# Sheet1.net
KiCad netlist of a schematic drawn in Altium Designer
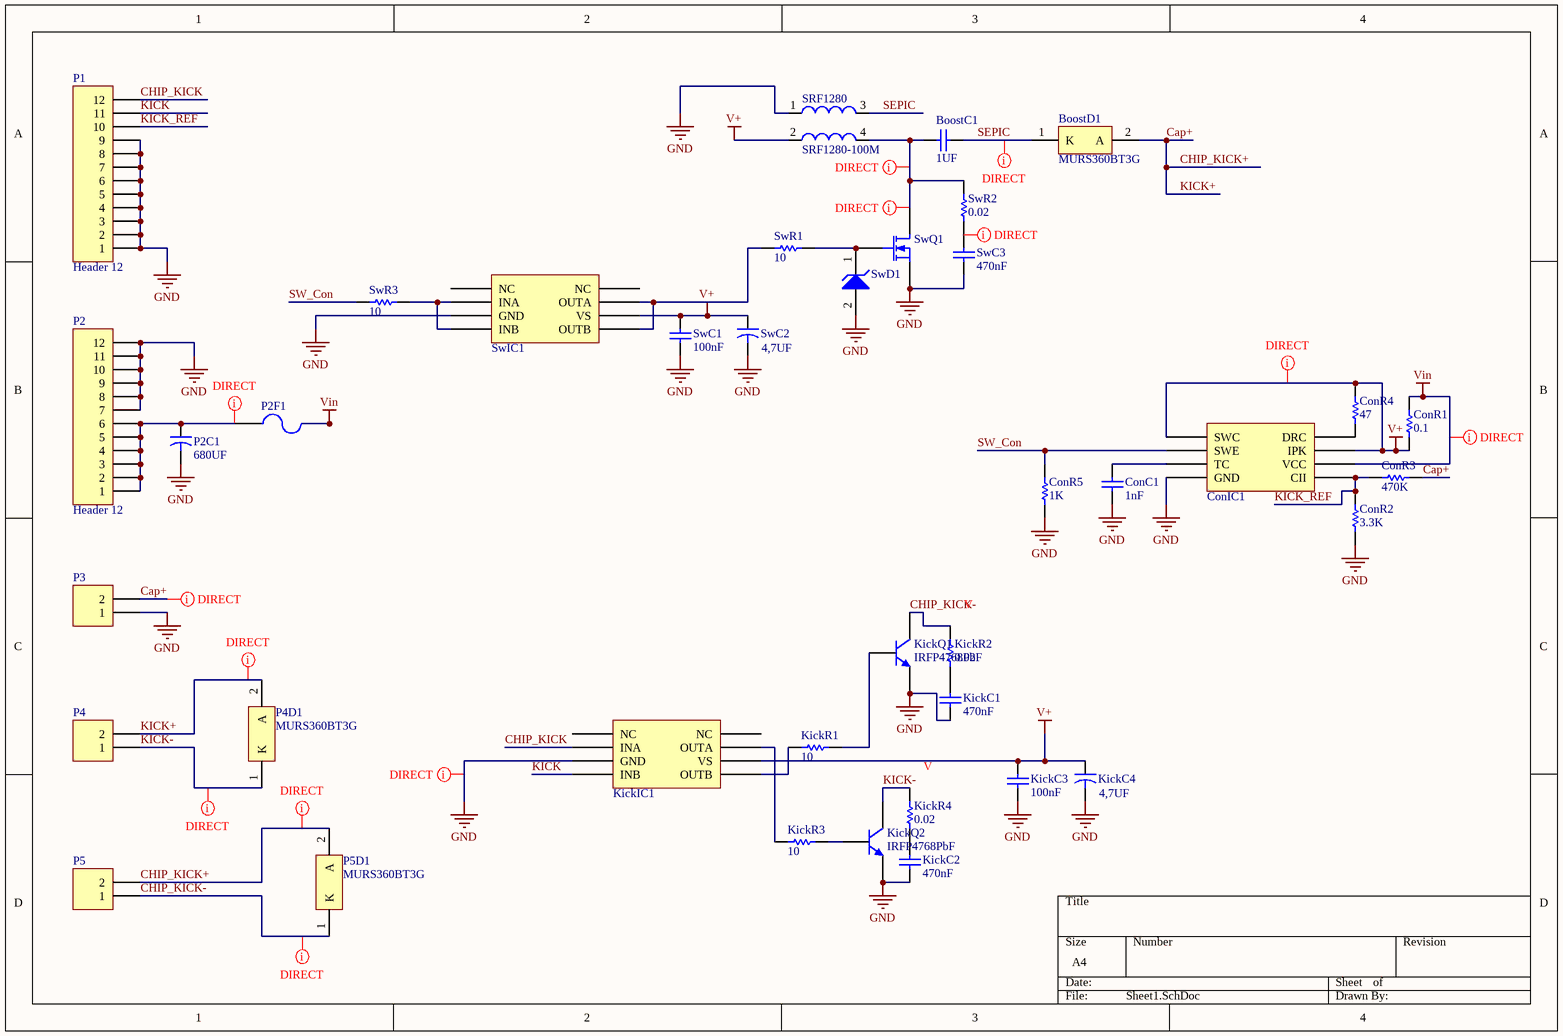
[diagram p0: Sheet1.SchDoc]

(export (version "E")
  (design (tool "Eeschema 10.0.6"))
  (components
    (comp (ref "BoostC1")
      (value "1UF")
      (footprint "CAP-2220")
      (description "1µF 450V Ceramic Capacitor X7T 2220 (5750 Metric) 0.224\" L x 0.197\" W (5.70mm x 5.00mm)")
      (fields (field (name "Comment") "CGA9P4X7T2W105M250KE"))
      (libsource (lib "Schlib1") (part "Cap 1UF 2220 450V"))
    )
    (comp (ref "BoostD1")
      (value "MURS360BT3G")
      (footprint "ONSC-SMB-2-403A-03_V")
      (description "Surface Mount Ultrafast Power Rectifier, 2-Pin SMB, Pb-Free, Tape and Reel")
      (fields (field (name "MANUFACTURER") "On Semiconductor"))
      (libsource (lib "") (part "CMP-0902-00327-1_1"))
    )
    (comp (ref "ConC1")
      (value "1nF")
      (footprint "CAP-0402")
      (description "1000pF 50V Ceramic Capacitor X7R 0402 (1005 Metric) 0.039\" L x 0.020\" W (1.00mm x 0.50mm)")
      (fields (field (name "Comment") "GRM155R71H102KA01D"))
      (libsource (lib "Schlib1") (part "Cap 1nF 0402"))
    )
    (comp (ref "ConIC1")
      (value "MC34063ACD")
      (footprint "SOIC8-STM")
      (libsource (lib "Schlib1") (part "MC34063ACD"))
    )
    (comp (ref "ConR1")
      (value "0.1")
      (footprint "RES-2512 BOURNS CRA")
      (description "RES SMD 0.1 OHM 1% 3W 2512")
      (fields (field (name "Comment") "CRA2512-FZ-R100ELF"))
      (libsource (lib "Schlib1") (part "RES 0R1 2512"))
    )
    (comp (ref "ConR2")
      (value "3.3K")
      (footprint "RES-1206")
      (description "RES SMD 3.3K OHM 5% 1/4W 1206")
      (fields (field (name "Comment") "RC1206JR-073K3L"))
      (libsource (lib "Schlib1") (part "RES 3.3K 1206"))
    )
    (comp (ref "ConR3")
      (value "470K")
      (footprint "RES-1206")
      (description "RES SMD 470K OHM 1% 1/4W 1206")
      (fields (field (name "Comment") "RC1206FR-07470KL"))
      (libsource (lib "Schlib1") (part "RES 470K 1206"))
    )
    (comp (ref "ConR4")
      (value "47")
      (footprint "RES-0402")
      (description "RES SMD 47 OHM 5% 1/16W 0402")
      (fields (field (name "Comment") "RC0402JR-0747RL"))
      (libsource (lib "Schlib1") (part "RES 47 0402"))
    )
    (comp (ref "ConR5")
      (value "1K")
      (footprint "RES-0402")
      (description "RES SMD 1K OHM 5% 1/16W 0402")
      (fields (field (name "Comment") "RC0402JR-071KL"))
      (libsource (lib "Schlib1") (part "RES 1K 0402"))
    )
    (comp (ref "KickC1")
      (value "470nF")
      (footprint "CAP-1812 TDK")
      (description "0.47µF 250V Ceramic Capacitor X7R 1812 (4532 Metric) 0.177\" L x 0.126\" W (4.50mm x 3.20mm)")
      (fields (field (name "Comment") "C4532X7R2E474K230KA"))
      (libsource (lib "Schlib1") (part "Cap 470nF 250V 1812"))
    )
    (comp (ref "KickC2")
      (value "470nF")
      (footprint "CAP-1812 TDK")
      (description "0.47µF 250V Ceramic Capacitor X7R 1812 (4532 Metric) 0.177\" L x 0.126\" W (4.50mm x 3.20mm)")
      (fields (field (name "Comment") "C4532X7R2E474K230KA"))
      (libsource (lib "Schlib1") (part "Cap 470nF 250V 1812"))
    )
    (comp (ref "KickC3")
      (value "100nF")
      (footprint "CAP-0402")
      (description "0.10µF 16V Ceramic Capacitor X7R 0402 (1005 Metric) 0.039\" L x 0.020\" W (1.00mm x 0.50mm)")
      (fields (field (name "Comment") "GRM155R71C104KA88D"))
      (libsource (lib "Schlib1") (part "Cap 100nF 0402"))
    )
    (comp (ref "KickC4")
      (value "4,7UF")
      (footprint "CAP Tant 1206 Kemet")
      (fields (field (name "Comment") "T491A475M025AT"))
      (libsource (lib "Schlib1") (part "Cap Tant 4,7UF 1206"))
    )
    (comp (ref "KickIC1")
      (value "IR4427STRPBF")
      (footprint "SOIC8-INFINEON")
      (description "IC DRIVER DUAL LOW SIDE 8SOIC")
      (libsource (lib "Schlib1") (part "IR4427"))
    )
    (comp (ref "KickQ1")
      (value "IRFP4768PbF")
      (footprint "TO-247AC")
      (description "MOSFET N-CH 250V 93A TO-247AC")
      (libsource (lib "Schlib1") (part "IRG4PC50FD"))
    )
    (comp (ref "KickQ2")
      (value "IRFP4768PbF")
      (footprint "TO-247AC")
      (description "MOSFET N-CH 250V 93A TO-247AC")
      (libsource (lib "Schlib1") (part "IRG4PC50FD"))
    )
    (comp (ref "KickR1")
      (value "10")
      (footprint "RES-0402")
      (description "RES SMD 10 OHM 5% 1/16W 0402")
      (fields (field (name "Comment") "RC0402JR-0710RL"))
      (libsource (lib "Schlib1") (part "RES 10 0402"))
    )
    (comp (ref "KickR2")
      (value "0.02")
      (footprint "RES-1206")
      (description "RES SMD 0.02 OHM 1% 1/4W 1206")
      (fields (field (name "Comment") "PF1206FRF070R02L"))
      (libsource (lib "Schlib1") (part "RES 0R02 1206"))
    )
    (comp (ref "KickR3")
      (value "10")
      (footprint "RES-0402")
      (description "RES SMD 10 OHM 5% 1/16W 0402")
      (fields (field (name "Comment") "RC0402JR-0710RL"))
      (libsource (lib "Schlib1") (part "RES 10 0402"))
    )
    (comp (ref "KickR4")
      (value "0.02")
      (footprint "RES-1206")
      (description "RES SMD 0.02 OHM 1% 1/4W 1206")
      (fields (field (name "Comment") "PF1206FRF070R02L"))
      (libsource (lib "Schlib1") (part "RES 0R02 1206"))
    )
    (comp (ref "P1")
      (value "Header 12")
      (footprint "HDR1X12")
      (description "Header, 12-Pin")
      (fields (field (name "PUBLISHER") "Altium Limited"))
      (libsource (lib "Miscellaneous Connectors") (part "Header 12"))
    )
    (comp (ref "P2")
      (value "Header 12")
      (footprint "HDR1X12")
      (description "Header, 12-Pin")
      (fields (field (name "PUBLISHER") "Altium Limited"))
      (libsource (lib "Miscellaneous Connectors") (part "Header 12"))
    )
    (comp (ref "P2C1")
      (value "680UF")
      (footprint "Cap Al Size G - Panasonic")
      (description "Aluminum Electrolytic Capacitors - SMD Al Lytic Cap SMT FK Series 105C")
      (fields (field (name "Comment") "EEE-FK1C681GP"))
      (libsource (lib "Schlib1") (part "CAP AL 680UF/16V"))
    )
    (comp (ref "P2F1")
      (value "MF-MSMF250/16X-2")
      (footprint "1812-MSMF Bourns2")
      (description "PTC RESETTABLE")
      (libsource (lib "Schlib1") (part "MF-MSMF250/16X"))
    )
    (comp (ref "P3")
      (value "OSTTA024163")
      (footprint "Term Block 2P")
      (description "2 Position Wire to Board Terminal Block Horizontal with Board 0.200\" (5.08mm) Through Hole")
      (libsource (lib "Schlib1") (part "Term Block 2P"))
    )
    (comp (ref "P4")
      (value "OSTTA024163")
      (footprint "Term Block 2P")
      (description "2 Position Wire to Board Terminal Block Horizontal with Board 0.200\" (5.08mm) Through Hole")
      (libsource (lib "Schlib1") (part "Term Block 2P"))
    )
    (comp (ref "P4D1")
      (value "MURS360BT3G")
      (footprint "ONSC-SMB-2-403A-03_V")
      (description "Surface Mount Ultrafast Power Rectifier, 2-Pin SMB, Pb-Free, Tape and Reel")
      (fields (field (name "MANUFACTURER") "On Semiconductor"))
      (libsource (lib "Altium Content Vault") (part "CMP-0902-00327-1"))
    )
    (comp (ref "P5")
      (value "OSTTA024163")
      (footprint "Term Block 2P")
      (description "2 Position Wire to Board Terminal Block Horizontal with Board 0.200\" (5.08mm) Through Hole")
      (libsource (lib "Schlib1") (part "Term Block 2P"))
    )
    (comp (ref "P5D1")
      (value "MURS360BT3G")
      (footprint "ONSC-SMB-2-403A-03_V")
      (description "Surface Mount Ultrafast Power Rectifier, 2-Pin SMB, Pb-Free, Tape and Reel")
      (fields (field (name "MANUFACTURER") "On Semiconductor"))
      (libsource (lib "Altium Content Vault") (part "CMP-0902-00327-1"))
    )
    (comp (ref "SRF1280")
      (value "SRF1280-100M")
      (footprint "SRF1280-100M-PCB")
      (libsource (lib "Schlib1") (part "SRF1280-100M"))
    )
    (comp (ref "SwC1")
      (value "100nF")
      (footprint "CAP-0402")
      (description "0.10µF 16V Ceramic Capacitor X7R 0402 (1005 Metric) 0.039\" L x 0.020\" W (1.00mm x 0.50mm)")
      (fields (field (name "Comment") "GRM155R71C104KA88D"))
      (libsource (lib "Schlib1") (part "Cap 100nF 0402"))
    )
    (comp (ref "SwC2")
      (value "4,7UF")
      (footprint "CAP Tant 1206 Kemet")
      (fields (field (name "Comment") "T491A475M025AT"))
      (libsource (lib "Schlib1") (part "Cap Tant 4,7UF 1206"))
    )
    (comp (ref "SwC3")
      (value "470nF")
      (footprint "CAP-1206 KEMET")
      (description "0.47µF 50V Ceramic Capacitor X8L 1206 (3216 Metric) 0.126\" L x 0.063\" W (3.20mm x 1.60mm)")
      (fields (field (name "Comment") "C1206C474K5NACTU"))
      (libsource (lib "Schlib1") (part "Cap 470nF 50V 1206"))
    )
    (comp (ref "SwD1")
      (value "MMSZ18T1G")
      (footprint "ONSC-SOD-123-2-425-04_V")
      (description "Zener Voltage Regulator, 500 mW, 2-Pin SOD-123, Pb-Free, Tape and Reel")
      (fields (field (name "MANUFACTURER") "On Semiconductor"))
      (libsource (lib "Altium Content Vault") (part "CMP-1060-00279-1"))
    )
    (comp (ref "SwIC1")
      (value "IR4427STRPBF")
      (footprint "SOIC8-INFINEON")
      (description "IC DRIVER DUAL LOW SIDE 8SOIC")
      (libsource (lib "Schlib1") (part "IR4427"))
    )
    (comp (ref "SwQ1")
      (value "SUM45N25-58-E3")
      (footprint "TO-263 Vishay")
      (description "MOSFET N-CH 250V 45A D2PAK")
      (libsource (lib "Schlib1") (part "SUM45N25"))
    )
    (comp (ref "SwR1")
      (value "10")
      (footprint "RES-0402")
      (description "RES SMD 10 OHM 5% 1/16W 0402")
      (fields (field (name "Comment") "RC0402JR-0710RL"))
      (libsource (lib "Schlib1") (part "RES 10 0402"))
    )
    (comp (ref "SwR2")
      (value "0.02")
      (footprint "RES-1206")
      (description "RES SMD 0.02 OHM 1% 1/4W 1206")
      (fields (field (name "Comment") "PF1206FRF070R02L"))
      (libsource (lib "Schlib1") (part "RES 0R02 1206"))
    )
    (comp (ref "SwR3")
      (value "10")
      (footprint "RES-0402")
      (description "RES SMD 10 OHM 5% 1/16W 0402")
      (fields (field (name "Comment") "RC0402JR-0710RL"))
      (libsource (lib "Schlib1") (part "RES 10 0402"))
    )
  )
  (nets
    (net (code "1") (name "/CHIP_KICK") (class "Default")
      (node (ref "KickIC1") (pin "2") (pinfunction "INA_2") (pintype "passive"))
      (node (ref "P1") (pin "12") (pinfunction "12_12") (pintype "passive"))
    )
    (net (code "2") (name "/CHIP_KICK+") (class "Default")
      (node (ref "BoostD1") (pin "2") (pinfunction "A_2") (pintype "passive"))
      (node (ref "ConR3") (pin "2") (pinfunction "2_2") (pintype "passive"))
      (node (ref "P3") (pin "2") (pinfunction "2_2") (pintype "passive"))
      (node (ref "P4") (pin "2") (pinfunction "2_2") (pintype "passive"))
      (node (ref "P4D1") (pin "2") (pinfunction "A_2") (pintype "passive"))
      (node (ref "P5") (pin "2") (pinfunction "2_2") (pintype "passive"))
      (node (ref "P5D1") (pin "2") (pinfunction "A_2") (pintype "passive"))
    )
    (net (code "3") (name "/CHIP_KICK-") (class "Default")
      (node (ref "KickQ1") (pin "2") (pinfunction "C_2") (pintype "passive"))
      (node (ref "KickR2") (pin "2") (pinfunction "2_2") (pintype "passive"))
      (node (ref "P5") (pin "1") (pinfunction "1_1") (pintype "passive"))
      (node (ref "P5D1") (pin "1") (pinfunction "K_1") (pintype "passive"))
    )
    (net (code "4") (name "/KICK") (class "Default")
      (node (ref "KickIC1") (pin "4") (pinfunction "INB_4") (pintype "passive"))
      (node (ref "P1") (pin "11") (pinfunction "11_11") (pintype "passive"))
    )
    (net (code "5") (name "/KICK-") (class "Default")
      (node (ref "KickQ2") (pin "2") (pinfunction "C_2") (pintype "passive"))
      (node (ref "KickR4") (pin "2") (pinfunction "2_2") (pintype "passive"))
      (node (ref "P4") (pin "1") (pinfunction "1_1") (pintype "passive"))
      (node (ref "P4D1") (pin "1") (pinfunction "K_1") (pintype "passive"))
    )
    (net (code "6") (name "/KICK_REF") (class "Default")
      (node (ref "ConIC1") (pin "5") (pinfunction "CII_5") (pintype "passive"))
      (node (ref "ConR2") (pin "2") (pinfunction "2_2") (pintype "passive"))
      (node (ref "ConR3") (pin "1") (pinfunction "1_1") (pintype "passive"))
      (node (ref "P1") (pin "10") (pinfunction "10_10") (pintype "passive"))
    )
    (net (code "7") (name "/SEPIC") (class "Default")
      (node (ref "BoostC1") (pin "2") (pinfunction "2_2") (pintype "passive"))
      (node (ref "BoostD1") (pin "1") (pinfunction "K_1") (pintype "passive"))
      (node (ref "SRF1280") (pin "3") (pinfunction "3_3") (pintype "passive"))
    )
    (net (code "8") (name "/SW_Con") (class "Default")
      (node (ref "ConIC1") (pin "2") (pinfunction "SWE_2") (pintype "passive"))
      (node (ref "ConR5") (pin "2") (pinfunction "2_2") (pintype "passive"))
      (node (ref "SwR3") (pin "1") (pinfunction "1_1") (pintype "passive"))
    )
    (net (code "9") (name "GND") (class "Default")
      (node (ref "ConC1") (pin "1") (pinfunction "1_1") (pintype "passive"))
      (node (ref "ConIC1") (pin "4") (pinfunction "GND_4") (pintype "passive"))
      (node (ref "ConR2") (pin "1") (pinfunction "1_1") (pintype "passive"))
      (node (ref "ConR5") (pin "1") (pinfunction "1_1") (pintype "passive"))
      (node (ref "KickC1") (pin "1") (pinfunction "1_1") (pintype "passive"))
      (node (ref "KickC2") (pin "1") (pinfunction "1_1") (pintype "passive"))
      (node (ref "KickC3") (pin "1") (pinfunction "1_1") (pintype "passive"))
      (node (ref "KickC4") (pin "2") (pinfunction "2_2") (pintype "passive"))
      (node (ref "KickIC1") (pin "3") (pinfunction "GND_3") (pintype "passive"))
      (node (ref "KickQ1") (pin "3") (pinfunction "E_3") (pintype "passive"))
      (node (ref "KickQ2") (pin "3") (pinfunction "E_3") (pintype "passive"))
      (node (ref "P1") (pin "1") (pinfunction "1_1") (pintype "passive"))
      (node (ref "P1") (pin "2") (pinfunction "2_2") (pintype "passive"))
      (node (ref "P1") (pin "3") (pinfunction "3_3") (pintype "passive"))
      (node (ref "P1") (pin "4") (pinfunction "4_4") (pintype "passive"))
      (node (ref "P1") (pin "5") (pinfunction "5_5") (pintype "passive"))
      (node (ref "P1") (pin "6") (pinfunction "6_6") (pintype "passive"))
      (node (ref "P1") (pin "7") (pinfunction "7_7") (pintype "passive"))
      (node (ref "P1") (pin "8") (pinfunction "8_8") (pintype "passive"))
      (node (ref "P1") (pin "9") (pinfunction "9_9") (pintype "passive"))
      (node (ref "P2") (pin "10") (pinfunction "10_10") (pintype "passive"))
      (node (ref "P2") (pin "11") (pinfunction "11_11") (pintype "passive"))
      (node (ref "P2") (pin "12") (pinfunction "12_12") (pintype "passive"))
      (node (ref "P2") (pin "7") (pinfunction "7_7") (pintype "passive"))
      (node (ref "P2") (pin "8") (pinfunction "8_8") (pintype "passive"))
      (node (ref "P2") (pin "9") (pinfunction "9_9") (pintype "passive"))
      (node (ref "P2C1") (pin "2") (pinfunction "2_2") (pintype "passive"))
      (node (ref "P3") (pin "1") (pinfunction "1_1") (pintype "passive"))
      (node (ref "SRF1280") (pin "1") (pinfunction "1_1") (pintype "passive"))
      (node (ref "SwC1") (pin "1") (pinfunction "1_1") (pintype "passive"))
      (node (ref "SwC2") (pin "2") (pinfunction "2_2") (pintype "passive"))
      (node (ref "SwC3") (pin "1") (pinfunction "1_1") (pintype "passive"))
      (node (ref "SwD1") (pin "2") (pinfunction "A_2") (pintype "passive"))
      (node (ref "SwIC1") (pin "3") (pinfunction "GND_3") (pintype "passive"))
      (node (ref "SwQ1") (pin "3") (pinfunction "S_3") (pintype "passive"))
    )
    (net (code "10") (name "Net-(ConIC1-DRC)") (class "Default")
      (node (ref "ConIC1") (pin "8") (pinfunction "DRC_8") (pintype "passive"))
      (node (ref "ConR4") (pin "1") (pinfunction "1_1") (pintype "passive"))
    )
    (net (code "11") (name "Net-(ConIC1-TC)") (class "Default")
      (node (ref "ConC1") (pin "2") (pinfunction "2_2") (pintype "passive"))
      (node (ref "ConIC1") (pin "3") (pinfunction "TC_3") (pintype "passive"))
    )
    (net (code "12") (name "Net-(KickC1-Pad2)") (class "Default")
      (node (ref "KickC1") (pin "2") (pinfunction "2_2") (pintype "passive"))
      (node (ref "KickR2") (pin "1") (pinfunction "1_1") (pintype "passive"))
    )
    (net (code "13") (name "Net-(KickC2-Pad2)") (class "Default")
      (node (ref "KickC2") (pin "2") (pinfunction "2_2") (pintype "passive"))
      (node (ref "KickR4") (pin "1") (pinfunction "1_1") (pintype "passive"))
    )
    (net (code "14") (name "Net-(KickIC1-OUTA)") (class "Default")
      (node (ref "KickIC1") (pin "7") (pinfunction "OUTA_7") (pintype "passive"))
      (node (ref "KickR3") (pin "1") (pinfunction "1_1") (pintype "passive"))
    )
    (net (code "15") (name "Net-(KickIC1-OUTB)") (class "Default")
      (node (ref "KickIC1") (pin "5") (pinfunction "OUTB_5") (pintype "passive"))
      (node (ref "KickR1") (pin "1") (pinfunction "1_1") (pintype "passive"))
    )
    (net (code "16") (name "Net-(KickQ1-B)") (class "Default")
      (node (ref "KickQ1") (pin "1") (pinfunction "B_1") (pintype "passive"))
      (node (ref "KickR1") (pin "2") (pinfunction "2_2") (pintype "passive"))
    )
    (net (code "17") (name "Net-(KickQ2-B)") (class "Default")
      (node (ref "KickQ2") (pin "1") (pinfunction "B_1") (pintype "passive"))
      (node (ref "KickR3") (pin "2") (pinfunction "2_2") (pintype "passive"))
    )
    (net (code "18") (name "Net-(P2-Pad1)") (class "Default")
      (node (ref "P2") (pin "1") (pinfunction "1_1") (pintype "passive"))
      (node (ref "P2") (pin "2") (pinfunction "2_2") (pintype "passive"))
      (node (ref "P2") (pin "3") (pinfunction "3_3") (pintype "passive"))
      (node (ref "P2") (pin "4") (pinfunction "4_4") (pintype "passive"))
      (node (ref "P2") (pin "5") (pinfunction "5_5") (pintype "passive"))
      (node (ref "P2") (pin "6") (pinfunction "6_6") (pintype "passive"))
      (node (ref "P2C1") (pin "1") (pinfunction "1_1") (pintype "passive"))
      (node (ref "P2F1") (pin "1") (pinfunction "1_1") (pintype "passive"))
    )
    (net (code "19") (name "Net-(SwC3-Pad2)") (class "Default")
      (node (ref "SwC3") (pin "2") (pinfunction "2_2") (pintype "passive"))
      (node (ref "SwR2") (pin "1") (pinfunction "1_1") (pintype "passive"))
    )
    (net (code "20") (name "Net-(SwD1-K)") (class "Default")
      (node (ref "SwD1") (pin "1") (pinfunction "K_1") (pintype "passive"))
      (node (ref "SwQ1") (pin "1") (pinfunction "G_1") (pintype "passive"))
      (node (ref "SwR1") (pin "2") (pinfunction "2_2") (pintype "passive"))
    )
    (net (code "21") (name "Net-(SwIC1-INA)") (class "Default")
      (node (ref "SwIC1") (pin "2") (pinfunction "INA_2") (pintype "passive"))
      (node (ref "SwIC1") (pin "4") (pinfunction "INB_4") (pintype "passive"))
      (node (ref "SwR3") (pin "2") (pinfunction "2_2") (pintype "passive"))
    )
    (net (code "22") (name "Net-(SwIC1-OUTA)") (class "Default")
      (node (ref "SwIC1") (pin "5") (pinfunction "OUTB_5") (pintype "passive"))
      (node (ref "SwIC1") (pin "7") (pinfunction "OUTA_7") (pintype "passive"))
      (node (ref "SwR1") (pin "1") (pinfunction "1_1") (pintype "passive"))
    )
    (net (code "23") (name "Net-(SwQ1-D)") (class "Default")
      (node (ref "BoostC1") (pin "1") (pinfunction "1_1") (pintype "passive"))
      (node (ref "SRF1280") (pin "4") (pinfunction "4_4") (pintype "passive"))
      (node (ref "SwQ1") (pin "2") (pinfunction "D_2") (pintype "passive"))
      (node (ref "SwR2") (pin "2") (pinfunction "2_2") (pintype "passive"))
    )
    (net (code "24") (name "V+") (class "Default")
      (node (ref "ConIC1") (pin "1") (pinfunction "SWC_1") (pintype "passive"))
      (node (ref "ConIC1") (pin "7") (pinfunction "IPK_7") (pintype "passive"))
      (node (ref "ConR1") (pin "1") (pinfunction "1_1") (pintype "passive"))
      (node (ref "ConR4") (pin "2") (pinfunction "2_2") (pintype "passive"))
      (node (ref "KickC3") (pin "2") (pinfunction "2_2") (pintype "passive"))
      (node (ref "KickC4") (pin "1") (pinfunction "1_1") (pintype "passive"))
      (node (ref "KickIC1") (pin "6") (pinfunction "VS_6") (pintype "passive"))
      (node (ref "SRF1280") (pin "2") (pinfunction "2_2") (pintype "passive"))
      (node (ref "SwC1") (pin "2") (pinfunction "2_2") (pintype "passive"))
      (node (ref "SwC2") (pin "1") (pinfunction "1_1") (pintype "passive"))
      (node (ref "SwIC1") (pin "6") (pinfunction "VS_6") (pintype "passive"))
    )
    (net (code "25") (name "Vin") (class "Default")
      (node (ref "ConIC1") (pin "6") (pinfunction "VCC_6") (pintype "passive"))
      (node (ref "ConR1") (pin "2") (pinfunction "2_2") (pintype "passive"))
      (node (ref "P2F1") (pin "2") (pinfunction "2_2") (pintype "passive"))
    )
    (net (code "26") (name "unconnected-(KickIC1-NC-Pad1)") (class "Default")
      (node (ref "KickIC1") (pin "1") (pinfunction "NC_1") (pintype "passive"))
    )
    (net (code "27") (name "unconnected-(KickIC1-NC-Pad8)") (class "Default")
      (node (ref "KickIC1") (pin "8") (pinfunction "NC_8") (pintype "passive"))
    )
    (net (code "28") (name "unconnected-(SwIC1-NC-Pad1)") (class "Default")
      (node (ref "SwIC1") (pin "1") (pinfunction "NC_1") (pintype "passive"))
    )
    (net (code "29") (name "unconnected-(SwIC1-NC-Pad8)") (class "Default")
      (node (ref "SwIC1") (pin "8") (pinfunction "NC_8") (pintype "passive"))
    )
  )
)
